# core.net
KiCad netlist of a schematic drawn in EAGLE
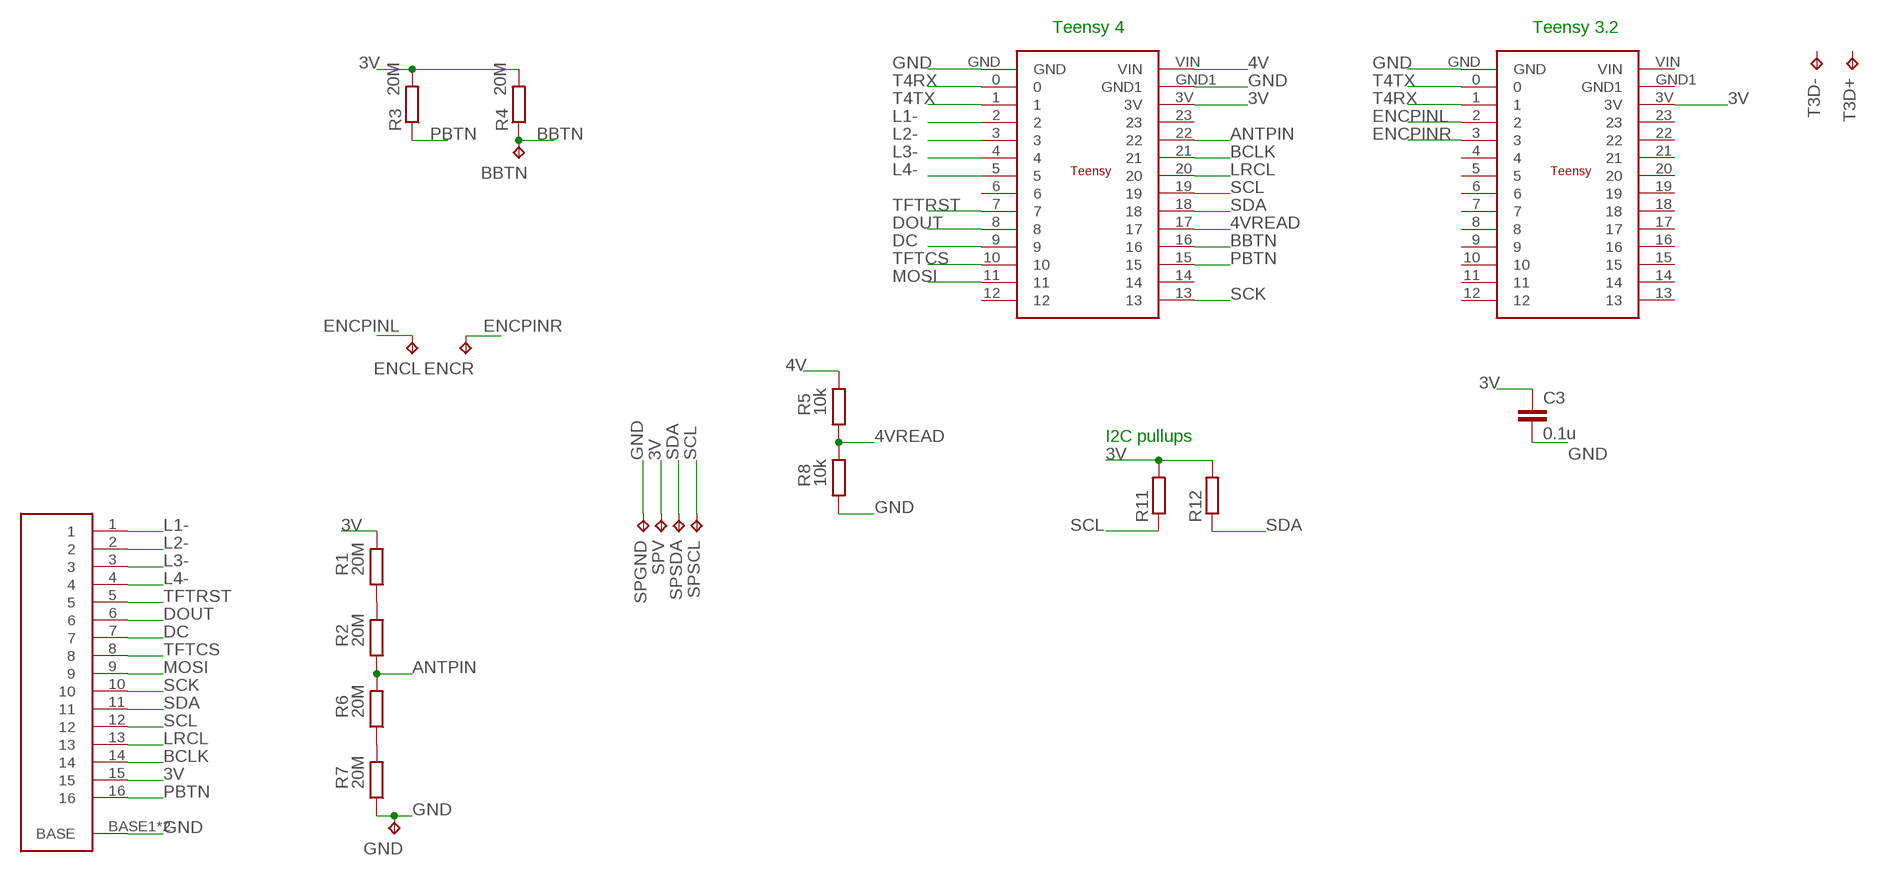
[diagram p0: schematic, sheet 1]

(export (version "E")
  (design (tool "Eeschema 10.0.6"))
  (components
    (comp (ref "BBTN")
      (value "TPTP14R")
      (footprint "eagle-import:TP14R")
      (libsource (lib "eagle-import") (part "TPTP14R"))
    )
    (comp (ref "C3")
      (value "0.1u")
      (footprint "eagle-import:C0805")
      (libsource (lib "eagle-import") (part "C-EUC0805"))
    )
    (comp (ref "ENCL")
      (value "TPTP14R")
      (footprint "eagle-import:TP14R")
      (libsource (lib "eagle-import") (part "TPTP14R"))
    )
    (comp (ref "ENCR")
      (value "TPTP14R")
      (footprint "eagle-import:TP14R")
      (libsource (lib "eagle-import") (part "TPTP14R"))
    )
    (comp (ref "GND")
      (value "TPTP14R")
      (footprint "eagle-import:TP14R")
      (libsource (lib "eagle-import") (part "TPTP14R"))
    )
    (comp (ref "R1")
      (value "20M")
      (footprint "eagle-import:M0805")
      (libsource (lib "eagle-import") (part "R-EU_M0805"))
    )
    (comp (ref "R2")
      (value "20M")
      (footprint "eagle-import:M0805")
      (libsource (lib "eagle-import") (part "R-EU_M0805"))
    )
    (comp (ref "R3")
      (value "20M")
      (footprint "eagle-import:M0805")
      (libsource (lib "eagle-import") (part "R-EU_M0805"))
    )
    (comp (ref "R4")
      (value "20M")
      (footprint "eagle-import:M0805")
      (libsource (lib "eagle-import") (part "R-EU_M0805"))
    )
    (comp (ref "R5")
      (value "10k")
      (footprint "eagle-import:M0805")
      (libsource (lib "eagle-import") (part "R-EU_M0805"))
    )
    (comp (ref "R6")
      (value "20M")
      (footprint "eagle-import:M0805")
      (libsource (lib "eagle-import") (part "R-EU_M0805"))
    )
    (comp (ref "R7")
      (value "20M")
      (footprint "eagle-import:M0805")
      (libsource (lib "eagle-import") (part "R-EU_M0805"))
    )
    (comp (ref "R8")
      (value "10k")
      (footprint "eagle-import:M0805")
      (libsource (lib "eagle-import") (part "R-EU_M0805"))
    )
    (comp (ref "R11")
      (value "R-EU_R0805")
      (footprint "eagle-import:R0805")
      (libsource (lib "eagle-import") (part "R-EU_R0805"))
    )
    (comp (ref "R12")
      (value "R-EU_R0805")
      (footprint "eagle-import:R0805")
      (libsource (lib "eagle-import") (part "R-EU_R0805"))
    )
    (comp (ref "SPGND")
      (value "TPTP14R")
      (footprint "eagle-import:TP14R")
      (libsource (lib "eagle-import") (part "TPTP14R"))
    )
    (comp (ref "SPSCL")
      (value "TPTP14R")
      (footprint "eagle-import:TP14R")
      (libsource (lib "eagle-import") (part "TPTP14R"))
    )
    (comp (ref "SPSDA")
      (value "TPTP14R")
      (footprint "eagle-import:TP14R")
      (libsource (lib "eagle-import") (part "TPTP14R"))
    )
    (comp (ref "SPV")
      (value "TPTP14R")
      (footprint "eagle-import:TP14R")
      (libsource (lib "eagle-import") (part "TPTP14R"))
    )
    (comp (ref "T3D+")
      (value "TPTP14R")
      (footprint "eagle-import:TP14R")
      (libsource (lib "eagle-import") (part "TPTP14R"))
    )
    (comp (ref "T3D-")
      (value "TPTP14R")
      (footprint "eagle-import:TP14R")
      (libsource (lib "eagle-import") (part "TPTP14R"))
    )
    (comp (ref "U$1")
      (value "TEENSY4")
      (footprint "eagle-import:TEENSYSMALL")
      (libsource (lib "eagle-import") (part "TEENSYSMALL"))
    )
    (comp (ref "U$2")
      (value "TEENSYSMALL")
      (footprint "eagle-import:TEENSYSMALL")
      (libsource (lib "eagle-import") (part "TEENSYSMALL"))
    )
    (comp (ref "U$3")
      (value "16PINFFC")
      (footprint "eagle-import:16PINFFC")
      (libsource (lib "eagle-import") (part "16PINFFC"))
    )
  )
  (nets
    (net (code "1") (name "/3V") (class "Default")
      (node (ref "C3") (pin "1") (pinfunction "1_1") (pintype "passive"))
      (node (ref "R1") (pin "2") (pinfunction "2_2") (pintype "passive"))
      (node (ref "R11") (pin "2") (pinfunction "2_2") (pintype "passive"))
      (node (ref "R12") (pin "2") (pinfunction "2_2") (pintype "passive"))
      (node (ref "R3") (pin "2") (pinfunction "2_2") (pintype "passive"))
      (node (ref "R4") (pin "2") (pinfunction "2_2") (pintype "passive"))
      (node (ref "SPV") (pin "TP") (pinfunction "TP_TP") (pintype "input"))
      (node (ref "U$1") (pin "3V") (pinfunction "3V_3V") (pintype "bidirectional"))
      (node (ref "U$2") (pin "3V") (pinfunction "3V_3V") (pintype "bidirectional"))
      (node (ref "U$3") (pin "15") (pinfunction "15_15") (pintype "bidirectional"))
    )
    (net (code "2") (name "/4V") (class "Default")
      (node (ref "R5") (pin "2") (pinfunction "2_2") (pintype "passive"))
      (node (ref "U$1") (pin "VIN") (pinfunction "VIN_VIN") (pintype "bidirectional"))
    )
    (net (code "3") (name "/4VREAD") (class "Default")
      (node (ref "R5") (pin "1") (pinfunction "1_1") (pintype "passive"))
      (node (ref "R8") (pin "2") (pinfunction "2_2") (pintype "passive"))
      (node (ref "U$1") (pin "17") (pinfunction "17_17") (pintype "bidirectional"))
    )
    (net (code "4") (name "/ANTPIN") (class "Default")
      (node (ref "R2") (pin "1") (pinfunction "1_1") (pintype "passive"))
      (node (ref "R6") (pin "2") (pinfunction "2_2") (pintype "passive"))
      (node (ref "U$1") (pin "22") (pinfunction "22_22") (pintype "bidirectional"))
    )
    (net (code "5") (name "/BBTN") (class "Default")
      (node (ref "BBTN") (pin "TP") (pinfunction "TP_TP") (pintype "input"))
      (node (ref "R4") (pin "1") (pinfunction "1_1") (pintype "passive"))
      (node (ref "U$1") (pin "16") (pinfunction "16_16") (pintype "bidirectional"))
    )
    (net (code "6") (name "/BCLK") (class "Default")
      (node (ref "U$1") (pin "21") (pinfunction "21_21") (pintype "bidirectional"))
      (node (ref "U$3") (pin "14") (pinfunction "14_14") (pintype "bidirectional"))
    )
    (net (code "7") (name "/DC") (class "Default")
      (node (ref "U$1") (pin "9") (pinfunction "9_9") (pintype "bidirectional"))
      (node (ref "U$3") (pin "7") (pinfunction "7_7") (pintype "bidirectional"))
    )
    (net (code "8") (name "/DOUT") (class "Default")
      (node (ref "U$1") (pin "8") (pinfunction "8_8") (pintype "bidirectional"))
      (node (ref "U$3") (pin "6") (pinfunction "6_6") (pintype "bidirectional"))
    )
    (net (code "9") (name "/ENCPINL") (class "Default")
      (node (ref "ENCL") (pin "TP") (pinfunction "TP_TP") (pintype "input"))
      (node (ref "U$2") (pin "2") (pinfunction "2_2") (pintype "bidirectional"))
    )
    (net (code "10") (name "/ENCPINR") (class "Default")
      (node (ref "ENCR") (pin "TP") (pinfunction "TP_TP") (pintype "input"))
      (node (ref "U$2") (pin "3") (pinfunction "3_3") (pintype "bidirectional"))
    )
    (net (code "11") (name "/GND") (class "Default")
      (node (ref "C3") (pin "2") (pinfunction "2_2") (pintype "passive"))
      (node (ref "GND") (pin "TP") (pinfunction "TP_TP") (pintype "input"))
      (node (ref "R7") (pin "1") (pinfunction "1_1") (pintype "passive"))
      (node (ref "R8") (pin "1") (pinfunction "1_1") (pintype "passive"))
      (node (ref "SPGND") (pin "TP") (pinfunction "TP_TP") (pintype "input"))
      (node (ref "U$1") (pin "GND") (pinfunction "GND_GND") (pintype "bidirectional"))
      (node (ref "U$1") (pin "GND1") (pinfunction "GND1_GND1") (pintype "bidirectional"))
      (node (ref "U$2") (pin "GND") (pinfunction "GND_GND") (pintype "bidirectional"))
      (node (ref "U$3") (pin "BASE1") (pinfunction "BASE_BASE1") (pintype "bidirectional"))
      (node (ref "U$3") (pin "BASE2") (pinfunction "BASE_BASE2") (pintype "bidirectional"))
    )
    (net (code "12") (name "/L1-") (class "Default")
      (node (ref "U$1") (pin "2") (pinfunction "2_2") (pintype "bidirectional"))
      (node (ref "U$3") (pin "1") (pinfunction "1_1") (pintype "bidirectional"))
    )
    (net (code "13") (name "/L2-") (class "Default")
      (node (ref "U$1") (pin "3") (pinfunction "3_3") (pintype "bidirectional"))
      (node (ref "U$3") (pin "2") (pinfunction "2_2") (pintype "bidirectional"))
    )
    (net (code "14") (name "/L3-") (class "Default")
      (node (ref "U$1") (pin "4") (pinfunction "4_4") (pintype "bidirectional"))
      (node (ref "U$3") (pin "3") (pinfunction "3_3") (pintype "bidirectional"))
    )
    (net (code "15") (name "/L4-") (class "Default")
      (node (ref "U$1") (pin "5") (pinfunction "5_5") (pintype "bidirectional"))
      (node (ref "U$3") (pin "4") (pinfunction "4_4") (pintype "bidirectional"))
    )
    (net (code "16") (name "/LRCL") (class "Default")
      (node (ref "U$1") (pin "20") (pinfunction "20_20") (pintype "bidirectional"))
      (node (ref "U$3") (pin "13") (pinfunction "13_13") (pintype "bidirectional"))
    )
    (net (code "17") (name "/MOSI") (class "Default")
      (node (ref "U$1") (pin "11") (pinfunction "11_11") (pintype "bidirectional"))
      (node (ref "U$3") (pin "9") (pinfunction "9_9") (pintype "bidirectional"))
    )
    (net (code "18") (name "/PBTN") (class "Default")
      (node (ref "R3") (pin "1") (pinfunction "1_1") (pintype "passive"))
      (node (ref "U$1") (pin "15") (pinfunction "15_15") (pintype "bidirectional"))
      (node (ref "U$3") (pin "16") (pinfunction "16_16") (pintype "bidirectional"))
    )
    (net (code "19") (name "/SCK") (class "Default")
      (node (ref "U$1") (pin "13") (pinfunction "13_13") (pintype "bidirectional"))
      (node (ref "U$3") (pin "10") (pinfunction "10_10") (pintype "bidirectional"))
    )
    (net (code "20") (name "/SCL") (class "Default")
      (node (ref "R11") (pin "1") (pinfunction "1_1") (pintype "passive"))
      (node (ref "SPSCL") (pin "TP") (pinfunction "TP_TP") (pintype "input"))
      (node (ref "U$1") (pin "19") (pinfunction "19_19") (pintype "bidirectional"))
      (node (ref "U$3") (pin "12") (pinfunction "12_12") (pintype "bidirectional"))
    )
    (net (code "21") (name "/SDA") (class "Default")
      (node (ref "R12") (pin "1") (pinfunction "1_1") (pintype "passive"))
      (node (ref "SPSDA") (pin "TP") (pinfunction "TP_TP") (pintype "input"))
      (node (ref "U$1") (pin "18") (pinfunction "18_18") (pintype "bidirectional"))
      (node (ref "U$3") (pin "11") (pinfunction "11_11") (pintype "bidirectional"))
    )
    (net (code "22") (name "/T4RX") (class "Default")
      (node (ref "U$1") (pin "0") (pinfunction "0_0") (pintype "bidirectional"))
      (node (ref "U$2") (pin "1") (pinfunction "1_1") (pintype "bidirectional"))
    )
    (net (code "23") (name "/T4TX") (class "Default")
      (node (ref "U$1") (pin "1") (pinfunction "1_1") (pintype "bidirectional"))
      (node (ref "U$2") (pin "0") (pinfunction "0_0") (pintype "bidirectional"))
    )
    (net (code "24") (name "/TFTCS") (class "Default")
      (node (ref "U$1") (pin "10") (pinfunction "10_10") (pintype "bidirectional"))
      (node (ref "U$3") (pin "8") (pinfunction "8_8") (pintype "bidirectional"))
    )
    (net (code "25") (name "/TFTRST") (class "Default")
      (node (ref "U$1") (pin "7") (pinfunction "7_7") (pintype "bidirectional"))
      (node (ref "U$3") (pin "5") (pinfunction "5_5") (pintype "bidirectional"))
    )
    (net (code "26") (name "Net-(R1-Pad1)") (class "Default")
      (node (ref "R1") (pin "1") (pinfunction "1_1") (pintype "passive"))
      (node (ref "R2") (pin "2") (pinfunction "2_2") (pintype "passive"))
    )
    (net (code "27") (name "Net-(R6-Pad1)") (class "Default")
      (node (ref "R6") (pin "1") (pinfunction "1_1") (pintype "passive"))
      (node (ref "R7") (pin "2") (pinfunction "2_2") (pintype "passive"))
    )
    (net (code "28") (name "unconnected-(T3D+-PadTP)") (class "Default")
      (node (ref "T3D+") (pin "TP") (pinfunction "TP_TP") (pintype "input"))
    )
    (net (code "29") (name "unconnected-(T3D--PadTP)") (class "Default")
      (node (ref "T3D-") (pin "TP") (pinfunction "TP_TP") (pintype "input"))
    )
    (net (code "30") (name "unconnected-(U$1-Pad6)") (class "Default")
      (node (ref "U$1") (pin "6") (pinfunction "6_6") (pintype "bidirectional"))
    )
    (net (code "31") (name "unconnected-(U$1-Pad12)") (class "Default")
      (node (ref "U$1") (pin "12") (pinfunction "12_12") (pintype "bidirectional"))
    )
    (net (code "32") (name "unconnected-(U$1-Pad14)") (class "Default")
      (node (ref "U$1") (pin "14") (pinfunction "14_14") (pintype "bidirectional"))
    )
    (net (code "33") (name "unconnected-(U$1-Pad23)") (class "Default")
      (node (ref "U$1") (pin "23") (pinfunction "23_23") (pintype "bidirectional"))
    )
    (net (code "34") (name "unconnected-(U$2-Pad4)") (class "Default")
      (node (ref "U$2") (pin "4") (pinfunction "4_4") (pintype "bidirectional"))
    )
    (net (code "35") (name "unconnected-(U$2-Pad5)") (class "Default")
      (node (ref "U$2") (pin "5") (pinfunction "5_5") (pintype "bidirectional"))
    )
    (net (code "36") (name "unconnected-(U$2-Pad6)") (class "Default")
      (node (ref "U$2") (pin "6") (pinfunction "6_6") (pintype "bidirectional"))
    )
    (net (code "37") (name "unconnected-(U$2-Pad7)") (class "Default")
      (node (ref "U$2") (pin "7") (pinfunction "7_7") (pintype "bidirectional"))
    )
    (net (code "38") (name "unconnected-(U$2-Pad8)") (class "Default")
      (node (ref "U$2") (pin "8") (pinfunction "8_8") (pintype "bidirectional"))
    )
    (net (code "39") (name "unconnected-(U$2-Pad9)") (class "Default")
      (node (ref "U$2") (pin "9") (pinfunction "9_9") (pintype "bidirectional"))
    )
    (net (code "40") (name "unconnected-(U$2-Pad10)") (class "Default")
      (node (ref "U$2") (pin "10") (pinfunction "10_10") (pintype "bidirectional"))
    )
    (net (code "41") (name "unconnected-(U$2-Pad11)") (class "Default")
      (node (ref "U$2") (pin "11") (pinfunction "11_11") (pintype "bidirectional"))
    )
    (net (code "42") (name "unconnected-(U$2-Pad12)") (class "Default")
      (node (ref "U$2") (pin "12") (pinfunction "12_12") (pintype "bidirectional"))
    )
    (net (code "43") (name "unconnected-(U$2-Pad13)") (class "Default")
      (node (ref "U$2") (pin "13") (pinfunction "13_13") (pintype "bidirectional"))
    )
    (net (code "44") (name "unconnected-(U$2-Pad14)") (class "Default")
      (node (ref "U$2") (pin "14") (pinfunction "14_14") (pintype "bidirectional"))
    )
    (net (code "45") (name "unconnected-(U$2-Pad15)") (class "Default")
      (node (ref "U$2") (pin "15") (pinfunction "15_15") (pintype "bidirectional"))
    )
    (net (code "46") (name "unconnected-(U$2-Pad16)") (class "Default")
      (node (ref "U$2") (pin "16") (pinfunction "16_16") (pintype "bidirectional"))
    )
    (net (code "47") (name "unconnected-(U$2-Pad17)") (class "Default")
      (node (ref "U$2") (pin "17") (pinfunction "17_17") (pintype "bidirectional"))
    )
    (net (code "48") (name "unconnected-(U$2-Pad18)") (class "Default")
      (node (ref "U$2") (pin "18") (pinfunction "18_18") (pintype "bidirectional"))
    )
    (net (code "49") (name "unconnected-(U$2-Pad19)") (class "Default")
      (node (ref "U$2") (pin "19") (pinfunction "19_19") (pintype "bidirectional"))
    )
    (net (code "50") (name "unconnected-(U$2-Pad20)") (class "Default")
      (node (ref "U$2") (pin "20") (pinfunction "20_20") (pintype "bidirectional"))
    )
    (net (code "51") (name "unconnected-(U$2-Pad21)") (class "Default")
      (node (ref "U$2") (pin "21") (pinfunction "21_21") (pintype "bidirectional"))
    )
    (net (code "52") (name "unconnected-(U$2-Pad22)") (class "Default")
      (node (ref "U$2") (pin "22") (pinfunction "22_22") (pintype "bidirectional"))
    )
    (net (code "53") (name "unconnected-(U$2-Pad23)") (class "Default")
      (node (ref "U$2") (pin "23") (pinfunction "23_23") (pintype "bidirectional"))
    )
    (net (code "54") (name "unconnected-(U$2-PadGND1)") (class "Default")
      (node (ref "U$2") (pin "GND1") (pinfunction "GND1_GND1") (pintype "bidirectional"))
    )
    (net (code "55") (name "unconnected-(U$2-PadVIN)") (class "Default")
      (node (ref "U$2") (pin "VIN") (pinfunction "VIN_VIN") (pintype "bidirectional"))
    )
  )
)
